# Flicker_Fusion.net
KiCad netlist of a schematic drawn in EAGLE
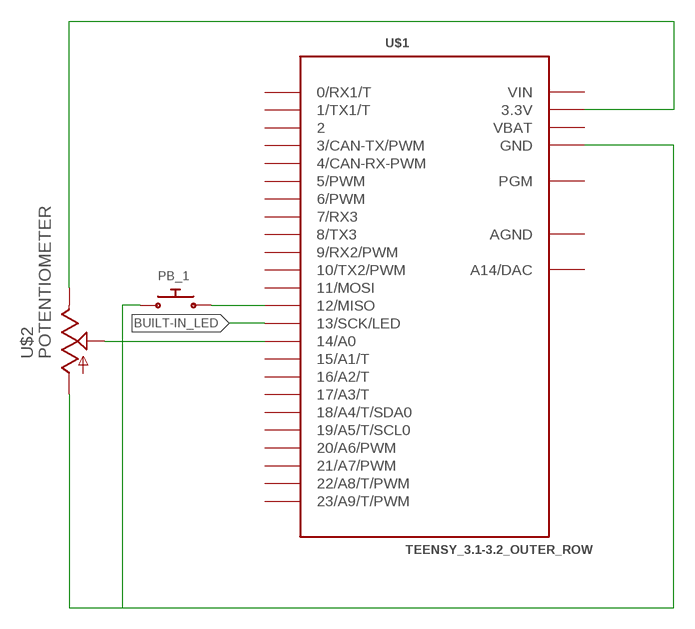
[diagram p0: schematic, sheet 1]

(export (version "E")
  (design (tool "Eeschema 10.0.6"))
  (components
    (comp (ref "PB_1")
      (value "PUSH_BUTTON_RCTNG")
      (footprint "eagle-import:PB_DIP_RCTNG_3-WIDE")
      (libsource (lib "eagle-import") (part "PUSH_BUTTON_RCTNG"))
    )
    (comp (ref "U$1")
      (value "TEENSY_3.1-3.2_OUTER_ROW")
      (footprint "eagle-import:TEENSY_3.0-3.2&LC_OUTER_ROW")
      (libsource (lib "eagle-import") (part "TEENSY_3.1-3.2_OUTER_ROW"))
    )
    (comp (ref "U$2")
      (value "POTENTIOMETER")
      (footprint "eagle-import:POTENTIOMETER")
      (libsource (lib "eagle-import") (part "POTENTIOMETER"))
    )
  )
  (nets
    (net (code "1") (name "/AGND") (class "Default")
      (node (ref "U$1") (pin "AGND") (pinfunction "AGND_AGND") (pintype "power_in"))
    )
    (net (code "2") (name "/VBAT") (class "Default")
      (node (ref "U$1") (pin "VBAT") (pinfunction "VBAT_VBAT") (pintype "power_in"))
    )
    (net (code "3") (name "/VIN") (class "Default")
      (node (ref "U$1") (pin "VIN") (pinfunction "VIN_VIN") (pintype "power_in"))
    )
    (net (code "4") (name "BUILT-IN_LED") (class "Default")
      (node (ref "U$1") (pin "13") (pinfunction "13/SCK/LED_13") (pintype "bidirectional"))
    )
    (net (code "5") (name "Net-(PB_1-P$1)") (class "Default")
      (node (ref "PB_1") (pin "1") (pinfunction "P$1_1") (pintype "passive"))
      (node (ref "U$1") (pin "GND") (pinfunction "GND_GND") (pintype "power_in"))
      (node (ref "U$1") (pin "GND1") (pinfunction "GND_GND1") (pintype "power_in"))
      (node (ref "U$2") (pin "+") (pinfunction "-_+") (pintype "passive"))
    )
    (net (code "6") (name "Net-(PB_1-P$2)") (class "Default")
      (node (ref "PB_1") (pin "2") (pinfunction "P$2_2") (pintype "passive"))
      (node (ref "U$1") (pin "12") (pinfunction "12/MISO_12") (pintype "bidirectional"))
    )
    (net (code "7") (name "Net-(U$1-Pad14{slash}A0)") (class "Default")
      (node (ref "U$1") (pin "14/A0") (pinfunction "14/A0_14/A0") (pintype "bidirectional"))
      (node (ref "U$2") (pin "DATA") (pinfunction "DATA_DATA") (pintype "passive"))
    )
    (net (code "8") (name "Net-(U$2-+)") (class "Default")
      (node (ref "U$1") (pin "3.3V") (pinfunction "3.3V_3.3V") (pintype "power_in"))
      (node (ref "U$1") (pin "3.3V1") (pinfunction "3.3V_3.3V1") (pintype "power_in"))
      (node (ref "U$2") (pin "-") (pinfunction "+_-") (pintype "passive"))
    )
    (net (code "9") (name "unconnected-(U$1-0{slash}RX1{slash}T-Pad0)") (class "Default")
      (node (ref "U$1") (pin "0") (pinfunction "0/RX1/T_0") (pintype "bidirectional"))
    )
    (net (code "10") (name "unconnected-(U$1-1{slash}TX1{slash}T-Pad1)") (class "Default")
      (node (ref "U$1") (pin "1") (pinfunction "1/TX1/T_1") (pintype "bidirectional"))
    )
    (net (code "11") (name "unconnected-(U$1-3{slash}CAN-TX{slash}PWM-Pad3)") (class "Default")
      (node (ref "U$1") (pin "3") (pinfunction "3/CAN-TX/PWM_3") (pintype "bidirectional"))
    )
    (net (code "12") (name "unconnected-(U$1-4{slash}CAN-RX-PWM-Pad4)") (class "Default")
      (node (ref "U$1") (pin "4") (pinfunction "4/CAN-RX-PWM_4") (pintype "bidirectional"))
    )
    (net (code "13") (name "unconnected-(U$1-5{slash}PWM-Pad5)") (class "Default")
      (node (ref "U$1") (pin "5") (pinfunction "5/PWM_5") (pintype "bidirectional"))
    )
    (net (code "14") (name "unconnected-(U$1-6{slash}PWM-Pad6)") (class "Default")
      (node (ref "U$1") (pin "6") (pinfunction "6/PWM_6") (pintype "bidirectional"))
    )
    (net (code "15") (name "unconnected-(U$1-7{slash}RX3-Pad7)") (class "Default")
      (node (ref "U$1") (pin "7") (pinfunction "7/RX3_7") (pintype "bidirectional"))
    )
    (net (code "16") (name "unconnected-(U$1-8{slash}TX3-Pad8)") (class "Default")
      (node (ref "U$1") (pin "8") (pinfunction "8/TX3_8") (pintype "bidirectional"))
    )
    (net (code "17") (name "unconnected-(U$1-9{slash}RX2{slash}PWM-Pad9)") (class "Default")
      (node (ref "U$1") (pin "9") (pinfunction "9/RX2/PWM_9") (pintype "bidirectional"))
    )
    (net (code "18") (name "unconnected-(U$1-10{slash}TX2{slash}PWM-Pad10)") (class "Default")
      (node (ref "U$1") (pin "10") (pinfunction "10/TX2/PWM_10") (pintype "bidirectional"))
    )
    (net (code "19") (name "unconnected-(U$1-11{slash}MOSI-Pad11)") (class "Default")
      (node (ref "U$1") (pin "11") (pinfunction "11/MOSI_11") (pintype "bidirectional"))
    )
    (net (code "20") (name "unconnected-(U$1-15{slash}A1{slash}T-Pad15{slash}A1)") (class "Default")
      (node (ref "U$1") (pin "15/A1") (pinfunction "15/A1/T_15/A1") (pintype "bidirectional"))
    )
    (net (code "21") (name "unconnected-(U$1-16{slash}A2{slash}T-Pad16{slash}A2)") (class "Default")
      (node (ref "U$1") (pin "16/A2") (pinfunction "16/A2/T_16/A2") (pintype "bidirectional"))
    )
    (net (code "22") (name "unconnected-(U$1-17{slash}A3{slash}T-Pad17{slash}A3)") (class "Default")
      (node (ref "U$1") (pin "17/A3") (pinfunction "17/A3/T_17/A3") (pintype "bidirectional"))
    )
    (net (code "23") (name "unconnected-(U$1-18{slash}A4{slash}T{slash}SDA0-Pad18{slash}A4)") (class "Default")
      (node (ref "U$1") (pin "18/A4") (pinfunction "18/A4/T/SDA0_18/A4") (pintype "bidirectional"))
    )
    (net (code "24") (name "unconnected-(U$1-19{slash}A5{slash}T{slash}SCL0-Pad19{slash}A5)") (class "Default")
      (node (ref "U$1") (pin "19/A5") (pinfunction "19/A5/T/SCL0_19/A5") (pintype "bidirectional"))
    )
    (net (code "25") (name "unconnected-(U$1-20{slash}A6{slash}PWM-Pad20{slash}A6)") (class "Default")
      (node (ref "U$1") (pin "20/A6") (pinfunction "20/A6/PWM_20/A6") (pintype "bidirectional"))
    )
    (net (code "26") (name "unconnected-(U$1-21{slash}A7{slash}PWM-Pad21{slash}A7)") (class "Default")
      (node (ref "U$1") (pin "21/A7") (pinfunction "21/A7/PWM_21/A7") (pintype "bidirectional"))
    )
    (net (code "27") (name "unconnected-(U$1-22{slash}A8{slash}T{slash}PWM-Pad22{slash}A8)") (class "Default")
      (node (ref "U$1") (pin "22/A8") (pinfunction "22/A8/T/PWM_22/A8") (pintype "bidirectional"))
    )
    (net (code "28") (name "unconnected-(U$1-23{slash}A9{slash}T{slash}PWM-Pad23{slash}A9)") (class "Default")
      (node (ref "U$1") (pin "23/A9") (pinfunction "23/A9/T/PWM_23/A9") (pintype "bidirectional"))
    )
    (net (code "29") (name "unconnected-(U$1-A14{slash}DAC-PadRESET{slash}DAC)") (class "Default")
      (node (ref "U$1") (pin "RESET/DAC") (pinfunction "A14/DAC_RESET/DAC") (pintype "bidirectional"))
    )
    (net (code "30") (name "unconnected-(U$1-Pad2)") (class "Default")
      (node (ref "U$1") (pin "2") (pinfunction "2_2") (pintype "bidirectional"))
    )
    (net (code "31") (name "unconnected-(U$1-PadPGM)") (class "Default")
      (node (ref "U$1") (pin "PGM") (pinfunction "PGM_PGM") (pintype "bidirectional"))
    )
  )
)
